# Ethernet.net
KiCad netlist of a schematic drawn in Altium Designer
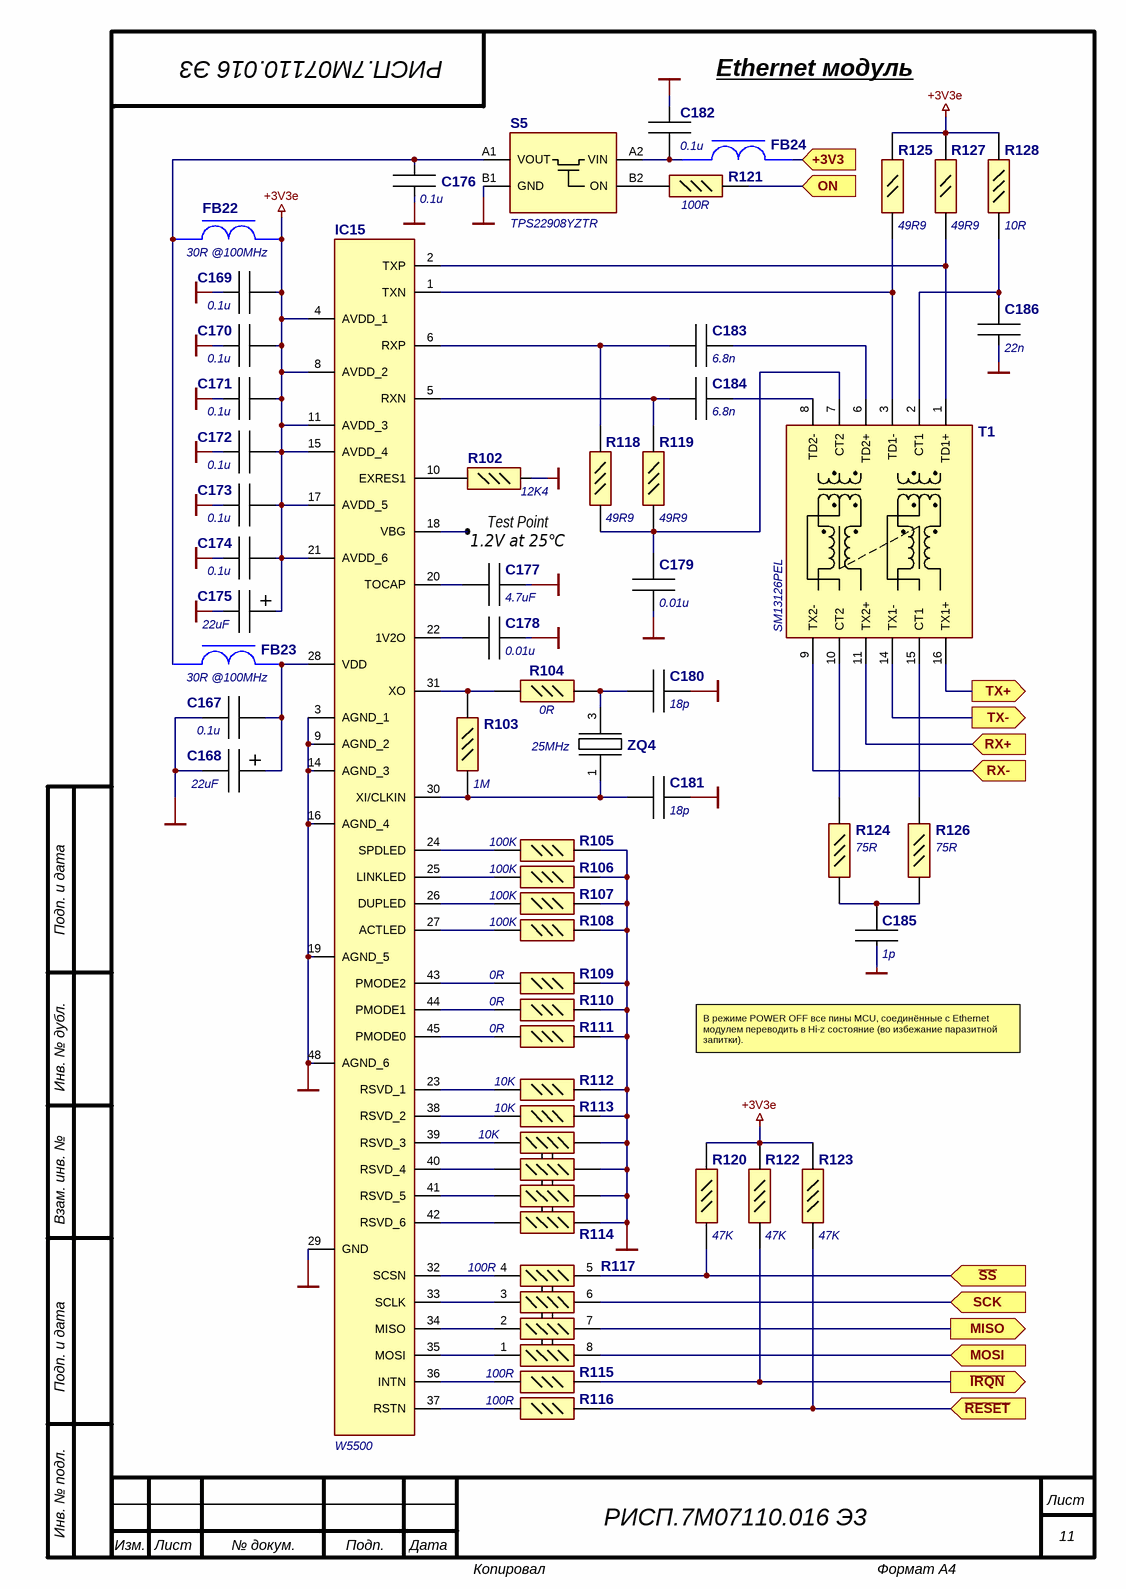
[diagram p0: Ethernet модуль.SchDoc]

(export (version "E")
  (design (tool "Eeschema 10.0.6"))
  (components
    (comp (ref "C167")
      (value "0.1u")
      (footprint ":CAP0402 100x50x50")
      (description "±10% 25V Ceramic Capacitor X7R 0402 (1005 Metric)")
      (fields
        (field (name "MANUFACTURER_PART_NUMBER") "GRM155R71E104KE14J")
        (field (name "MOUSER PART NUMBER") "81-GRM155R71E104KE4J")
      )
      (libsource (lib "Capacitors 0402") (part "GRM155R71E104KE14J"))
    )
    (comp (ref "C168")
      (value "22uF")
      (footprint ":CAP1206 C3216-18")
      (description "22µF Molded Tantalum Capacitors 6.3V 1206 (3216 Metric) 300mOhm @ 100kHz")
      (fields (field (name "MANUFACTURER_PART_NUMBER") "TPSA226K006R0300"))
      (libsource (lib "Capacitors 1206") (part "TPSA226K006R0300"))
    )
    (comp (ref "C169")
      (value "0.1u")
      (footprint ":CAP0402 100x50x50")
      (description "±10% 25V Ceramic Capacitor X7R 0402 (1005 Metric)")
      (fields
        (field (name "MANUFACTURER_PART_NUMBER") "GRM155R71E104KE14J")
        (field (name "MOUSER PART NUMBER") "81-GRM155R71E104KE4J")
      )
      (libsource (lib "Capacitors 0402") (part "GRM155R71E104KE14J"))
    )
    (comp (ref "C170")
      (value "0.1u")
      (footprint ":CAP0402 100x50x50")
      (description "±10% 25V Ceramic Capacitor X7R 0402 (1005 Metric)")
      (fields
        (field (name "MANUFACTURER_PART_NUMBER") "GRM155R71E104KE14J")
        (field (name "MOUSER PART NUMBER") "81-GRM155R71E104KE4J")
      )
      (libsource (lib "Capacitors 0402") (part "GRM155R71E104KE14J"))
    )
    (comp (ref "C171")
      (value "0.1u")
      (footprint ":CAP0402 100x50x50")
      (description "±10% 25V Ceramic Capacitor X7R 0402 (1005 Metric)")
      (fields
        (field (name "MANUFACTURER_PART_NUMBER") "GRM155R71E104KE14J")
        (field (name "MOUSER PART NUMBER") "81-GRM155R71E104KE4J")
      )
      (libsource (lib "Capacitors 0402") (part "GRM155R71E104KE14J"))
    )
    (comp (ref "C172")
      (value "0.1u")
      (footprint ":CAP0402 100x50x50")
      (description "±10% 25V Ceramic Capacitor X7R 0402 (1005 Metric)")
      (fields
        (field (name "MANUFACTURER_PART_NUMBER") "GRM155R71E104KE14J")
        (field (name "MOUSER PART NUMBER") "81-GRM155R71E104KE4J")
      )
      (libsource (lib "Capacitors 0402") (part "GRM155R71E104KE14J"))
    )
    (comp (ref "C173")
      (value "0.1u")
      (footprint ":CAP0402 100x50x50")
      (description "±10% 25V Ceramic Capacitor X7R 0402 (1005 Metric)")
      (fields
        (field (name "MANUFACTURER_PART_NUMBER") "GRM155R71E104KE14J")
        (field (name "MOUSER PART NUMBER") "81-GRM155R71E104KE4J")
      )
      (libsource (lib "Capacitors 0402") (part "GRM155R71E104KE14J"))
    )
    (comp (ref "C174")
      (value "0.1u")
      (footprint ":CAP0402 100x50x50")
      (description "±10% 25V Ceramic Capacitor X7R 0402 (1005 Metric)")
      (fields
        (field (name "MANUFACTURER_PART_NUMBER") "GRM155R71E104KE14J")
        (field (name "MOUSER PART NUMBER") "81-GRM155R71E104KE4J")
      )
      (libsource (lib "Capacitors 0402") (part "GRM155R71E104KE14J"))
    )
    (comp (ref "C175")
      (value "22uF")
      (footprint ":CAP1206 C3216-18")
      (description "22µF Molded Tantalum Capacitors 6.3V 1206 (3216 Metric) 300mOhm @ 100kHz")
      (fields (field (name "MANUFACTURER_PART_NUMBER") "TPSA226K006R0300"))
      (libsource (lib "Capacitors 1206") (part "TPSA226K006R0300"))
    )
    (comp (ref "C176")
      (value "0.1u")
      (footprint ":CAP0402 100x50x50")
      (description "±10% 25V Ceramic Capacitor X7R 0402 (1005 Metric)")
      (fields
        (field (name "MANUFACTURER_PART_NUMBER") "GRM155R71E104KE14J")
        (field (name "MOUSER PART NUMBER") "81-GRM155R71E104KE4J")
      )
      (libsource (lib "") (part "GRM155R71E104KE14J_1"))
    )
    (comp (ref "C177")
      (value "4.7uF")
      (footprint ":CAP0805 C2012X125")
      (description "CAP CER 4.7uF 25V X7R 0805")
      (fields (field (name "MANUFACTURER_PART_NUMBER") "GRM21BZ71E475KE15L"))
      (libsource (lib "Capacitors 0805") (part "GRM21BZ71E475KE15L"))
    )
    (comp (ref "C178")
      (value "0.01u")
      (footprint ":CAP0402 100x50x50")
      (description "±5% 35V Ceramic Capacitor C0G, NP0 0402 (1005 Metric)")
      (fields (field (name "MANUFACTURER_PART_NUMBER") "GRM1555CYA103JE01D"))
      (libsource (lib "Capacitors 0402") (part "GRM1555CYA103JE01D"))
    )
    (comp (ref "C179")
      (value "0.01u")
      (footprint ":CAP0402 100x50x50")
      (description "±5% 35V Ceramic Capacitor C0G, NP0 0402 (1005 Metric)")
      (fields (field (name "MANUFACTURER_PART_NUMBER") "GRM1555CYA103JE01D"))
      (libsource (lib "Capacitors 0402") (part "GRM1555CYA103JE01D"))
    )
    (comp (ref "C180")
      (value "18p")
      (footprint ":CAP0402 100x50x50")
      (description "CAP CER  50V C0G/NP0 0402")
      (fields (field (name "MANUFACTURER_PART_NUMBER") "GJM1555C1H180JB01D"))
      (libsource (lib "Capacitors 0402") (part "GJM1555C1H180JB01D"))
    )
    (comp (ref "C181")
      (value "18p")
      (footprint ":CAP0402 100x50x50")
      (description "CAP CER  50V C0G/NP0 0402")
      (fields (field (name "MANUFACTURER_PART_NUMBER") "GJM1555C1H180JB01D"))
      (libsource (lib "Capacitors 0402") (part "GJM1555C1H180JB01D"))
    )
    (comp (ref "C182")
      (value "0.1u")
      (footprint ":CAP0402 100x50x50")
      (description "±10% 25V Ceramic Capacitor X7R 0402 (1005 Metric)")
      (fields
        (field (name "MANUFACTURER_PART_NUMBER") "GRM155R71E104KE14J")
        (field (name "MOUSER PART NUMBER") "81-GRM155R71E104KE4J")
      )
      (libsource (lib "Capacitors 0402") (part "GRM155R71E104KE14J"))
    )
    (comp (ref "C183")
      (value "6.8n")
      (footprint ":CAP0402 100x50x50")
      (description "CAP CER  25V X7R 0402")
      (fields (field (name "MANUFACTURER_PART_NUMBER") "GCM155R71E682KA37D"))
      (libsource (lib "Capacitors 0402") (part "GCM155R71E682KA37D"))
    )
    (comp (ref "C184")
      (value "6.8n")
      (footprint ":CAP0402 100x50x50")
      (description "CAP CER  25V X7R 0402")
      (fields (field (name "MANUFACTURER_PART_NUMBER") "GCM155R71E682KA37D"))
      (libsource (lib "Capacitors 0402") (part "GCM155R71E682KA37D"))
    )
    (comp (ref "C185")
      (value "1p")
      (footprint ":CAP0402 100x50x50")
      (description "CAP CER  50V C0G/NP0 0402")
      (fields (field (name "MANUFACTURER_PART_NUMBER") "GJM1555C1H1R0BB01D"))
      (libsource (lib "Capacitors 0402") (part "GJM1555C1H1R0BB01D"))
    )
    (comp (ref "C186")
      (value "22n")
      (footprint ":CAP0402 100x50x50")
      (description "CAP CER  25V X7R 0402")
      (fields (field (name "MANUFACTURER_PART_NUMBER") "GCM155R71E223KA55D"))
      (libsource (lib "Capacitors 0402") (part "GCM155R71E223KA55D"))
    )
    (comp (ref "FB22")
      (value "30R @100MHz")
      (footprint ":FER BLM18SP300SN1D")
      (description "30 Ohms @ 100MHz 1 Power Line Ferrite Bead 0603 (1608 Metric) 6A 8mOhm")
      (fields
        (field (name "MANUFACTURER_PART_NUMBER") "BLM18SP300SN1D")
        (field (name "MOUSER PART NUMBER") "81-BLM18SP300SN1D")
      )
      (libsource (lib "Ferrite Bead") (part "BLM18SP300SN1D"))
    )
    (comp (ref "FB23")
      (value "30R @100MHz")
      (footprint ":FER BLM18SP300SN1D")
      (description "30 Ohms @ 100MHz 1 Power Line Ferrite Bead 0603 (1608 Metric) 6A 8mOhm")
      (fields
        (field (name "MANUFACTURER_PART_NUMBER") "BLM18SP300SN1D")
        (field (name "MOUSER PART NUMBER") "81-BLM18SP300SN1D")
      )
      (libsource (lib "Ferrite Bead") (part "BLM18SP300SN1D"))
    )
    (comp (ref "FB24")
      (value "30R @100MHz")
      (footprint ":FER BLM18SP300SN1D")
      (description "30 Ohms @ 100MHz 1 Power Line Ferrite Bead 0603 (1608 Metric) 6A 8mOhm")
      (fields
        (field (name "MANUFACTURER_PART_NUMBER") "BLM18SP300SN1D")
        (field (name "MOUSER PART NUMBER") "81-BLM18SP300SN1D")
      )
      (libsource (lib "Ferrite Bead") (part "BLM18SP300SN1D"))
    )
    (comp (ref "IC15")
      (value "W5500")
      (footprint ":QFP48 P900X900X160-48N")
      (description "Ethernet ICs 3in1 Enet Controller TCP/IP +MAC+PHY")
      (libsource (lib "Digital ICs") (part "W5500"))
    )
    (comp (ref "R102")
      (value "RC0402FR-07")
      (footprint ":RES0402")
      (fields (field (name "MANUFACTURER_PART_NUMBER (PART 2: VALUE)") "12K4"))
      (libsource (lib "Resistors 0402") (part "RC0402FR-07"))
    )
    (comp (ref "R103")
      (value "RC0402FR-07")
      (footprint ":RES0402")
      (fields (field (name "MANUFACTURER_PART_NUMBER (PART 2: VALUE)") "1M"))
      (libsource (lib "") (part "RC0402FR-07_3"))
    )
    (comp (ref "R104")
      (value "RC0402FR-07")
      (footprint ":RES0402")
      (fields (field (name "MANUFACTURER_PART_NUMBER (PART 2: VALUE)") "0R"))
      (libsource (lib "Resistors 0402") (part "RC0402FR-07"))
    )
    (comp (ref "R105")
      (value "RC0402FR-07")
      (footprint ":RES0402")
      (fields (field (name "MANUFACTURER_PART_NUMBER (PART 2: VALUE)") "100K"))
      (libsource (lib "Resistors 0402") (part "RC0402FR-07"))
    )
    (comp (ref "R106")
      (value "RC0402FR-07")
      (footprint ":RES0402")
      (fields (field (name "MANUFACTURER_PART_NUMBER (PART 2: VALUE)") "100K"))
      (libsource (lib "Resistors 0402") (part "RC0402FR-07"))
    )
    (comp (ref "R107")
      (value "RC0402FR-07")
      (footprint ":RES0402")
      (fields (field (name "MANUFACTURER_PART_NUMBER (PART 2: VALUE)") "100K"))
      (libsource (lib "Resistors 0402") (part "RC0402FR-07"))
    )
    (comp (ref "R108")
      (value "RC0402FR-07")
      (footprint ":RES0402")
      (fields (field (name "MANUFACTURER_PART_NUMBER (PART 2: VALUE)") "100K"))
      (libsource (lib "Resistors 0402") (part "RC0402FR-07"))
    )
    (comp (ref "R109")
      (value "RC0402FR-07")
      (footprint ":RES0402")
      (fields (field (name "MANUFACTURER_PART_NUMBER (PART 2: VALUE)") "0R"))
      (libsource (lib "Resistors 0402") (part "RC0402FR-07"))
    )
    (comp (ref "R110")
      (value "RC0402FR-07")
      (footprint ":RES0402")
      (fields (field (name "MANUFACTURER_PART_NUMBER (PART 2: VALUE)") "0R"))
      (libsource (lib "Resistors 0402") (part "RC0402FR-07"))
    )
    (comp (ref "R111")
      (value "RC0402FR-07")
      (footprint ":RES0402")
      (fields (field (name "MANUFACTURER_PART_NUMBER (PART 2: VALUE)") "0R"))
      (libsource (lib "Resistors 0402") (part "RC0402FR-07"))
    )
    (comp (ref "R112")
      (value "RC0402FR-07")
      (footprint ":RES0402")
      (fields (field (name "MANUFACTURER_PART_NUMBER (PART 2: VALUE)") "10K"))
      (libsource (lib "") (part "RC0402FR-07_1"))
    )
    (comp (ref "R113")
      (value "RC0402FR-07")
      (footprint ":RES0402")
      (fields (field (name "MANUFACTURER_PART_NUMBER (PART 2: VALUE)") "10K"))
      (libsource (lib "") (part "RC0402FR-07_1"))
    )
    (comp (ref "R114")
      (value "10K")
      (footprint ":RES0402x4")
      (fields (field (name "MANUFACTURER_PART_NUMBER") "EXB-N8V103JX"))
      (libsource (lib "Resistors Arrays") (part "EXB-N8V103JX"))
    )
    (comp (ref "R115")
      (value "RC0402FR-07")
      (footprint ":RES0402")
      (fields (field (name "MANUFACTURER_PART_NUMBER (PART 2: VALUE)") "100R"))
      (libsource (lib "Resistors 0402") (part "RC0402FR-07"))
    )
    (comp (ref "R116")
      (value "RC0402FR-07")
      (footprint ":RES0402")
      (fields (field (name "MANUFACTURER_PART_NUMBER (PART 2: VALUE)") "100R"))
      (libsource (lib "Resistors 0402") (part "RC0402FR-07"))
    )
    (comp (ref "R117")
      (value "100R")
      (footprint ":RES0402x4")
      (fields
        (field (name "MANUFACTURER_PART_NUMBER") "EXB-N8V101JX")
        (field (name "MOUSER PART NUMBER") "667-EXB-N8V101JX")
      )
      (libsource (lib "Resistors Arrays") (part "EXB-N8V101JX"))
    )
    (comp (ref "R118")
      (value "RC0402FR-07")
      (footprint ":RES0402")
      (fields (field (name "MANUFACTURER_PART_NUMBER (PART 2: VALUE)") "49R9"))
      (libsource (lib "") (part "RC0402FR-07_3"))
    )
    (comp (ref "R119")
      (value "RC0402FR-07")
      (footprint ":RES0402")
      (fields (field (name "MANUFACTURER_PART_NUMBER (PART 2: VALUE)") "49R9"))
      (libsource (lib "") (part "RC0402FR-07_3"))
    )
    (comp (ref "R120")
      (value "RC0402FR-07")
      (footprint ":RES0402")
      (fields (field (name "MANUFACTURER_PART_NUMBER (PART 2: VALUE)") "47K"))
      (libsource (lib "") (part "RC0402FR-07_3"))
    )
    (comp (ref "R121")
      (value "RC0402FR-07")
      (footprint ":RES0402")
      (fields (field (name "MANUFACTURER_PART_NUMBER (PART 2: VALUE)") "100R"))
      (libsource (lib "Resistors 0402") (part "RC0402FR-07"))
    )
    (comp (ref "R122")
      (value "RC0402FR-07")
      (footprint ":RES0402")
      (fields (field (name "MANUFACTURER_PART_NUMBER (PART 2: VALUE)") "47K"))
      (libsource (lib "") (part "RC0402FR-07_3"))
    )
    (comp (ref "R123")
      (value "RC0402FR-07")
      (footprint ":RES0402")
      (fields (field (name "MANUFACTURER_PART_NUMBER (PART 2: VALUE)") "47K"))
      (libsource (lib "") (part "RC0402FR-07_3"))
    )
    (comp (ref "R124")
      (value "RC0402FR-07")
      (footprint ":RES0402")
      (fields (field (name "MANUFACTURER_PART_NUMBER (PART 2: VALUE)") "75R"))
      (libsource (lib "") (part "RC0402FR-07_2"))
    )
    (comp (ref "R125")
      (value "49R9")
      (footprint ":RES0805")
      (description "49.9 Ohms ±1% 0.125W, 1/8W Chip Resistor 0805 (2012 Metric) Automotive AEC-Q200 Thick Film")
      (fields
        (field (name "MANUFACTURER_PART_NUMBER") "ERJ-6ENF49R9V")
        (field (name "MOUSER PART NUMBER") "667-ERJ-6ENF49R9V")
      )
      (libsource (lib "Resistors 0805") (part "ERJ-6ENF49R9V"))
    )
    (comp (ref "R126")
      (value "RC0402FR-07")
      (footprint ":RES0402")
      (fields (field (name "MANUFACTURER_PART_NUMBER (PART 2: VALUE)") "75R"))
      (libsource (lib "") (part "RC0402FR-07_2"))
    )
    (comp (ref "R127")
      (value "49R9")
      (footprint ":RES0805")
      (description "49.9 Ohms ±1% 0.125W, 1/8W Chip Resistor 0805 (2012 Metric) Automotive AEC-Q200 Thick Film")
      (fields
        (field (name "MANUFACTURER_PART_NUMBER") "ERJ-6ENF49R9V")
        (field (name "MOUSER PART NUMBER") "667-ERJ-6ENF49R9V")
      )
      (libsource (lib "Resistors 0805") (part "ERJ-6ENF49R9V"))
    )
    (comp (ref "R128")
      (value "RC0402FR-07")
      (footprint ":RES0402")
      (fields (field (name "MANUFACTURER_PART_NUMBER (PART 2: VALUE)") "10R"))
      (libsource (lib "") (part "RC0402FR-07_3"))
    )
    (comp (ref "S5")
      (value "TPS22908YZTR")
      (footprint ":BGA4 P90X90X50")
      (description "SPST Switch 3.6-V, 1-A, 28-mΩ")
      (fields (field (name "MOUSER PART NUMBER") "595-TPS22908YZTR"))
      (libsource (lib "Switching and Relays") (part "TPS22908YZTR"))
    )
    (comp (ref "T1")
      (value "SM13126PEL")
      (footprint ":TRAN SM13126PEL")
      (description "Transformers LAN 10/100 BASE-T")
      (fields (field (name "MOUSER PART NUMBER") "652-SM13126PEL"))
      (libsource (lib "Transformers") (part "SM13126PEL"))
    )
    (comp (ref "X3")
      (value "Big Circle Pad")
      (description "Большая круглая контактная площадка")
      (libsource (lib "Connectors") (part "Big Circle Pad"))
    )
    (comp (ref "ZQ4")
      (value "25MHz")
      (footprint ":RESO SXT22418FB48-25.000MT")
      (description "CRYSTAL 25MHz\r\n±10ppm Crystal 18pF 4-SMD\r\nESR: 80 Ohms")
      (fields (field (name "MANUFACTURER_PART_NUMBER") "SXT22418FB48-25.000MT"))
      (libsource (lib "Crystal and TXCO") (part "SXT22418FB48-25.000MT"))
    )
  )
  (nets
    (net (code "1") (name "+3V3e") (class "Default")
      (node (ref "C169") (pin "2") (pinfunction "2_2") (pintype "passive"))
      (node (ref "C170") (pin "2") (pinfunction "2_2") (pintype "passive"))
      (node (ref "C171") (pin "2") (pinfunction "2_2") (pintype "passive"))
      (node (ref "C172") (pin "2") (pinfunction "2_2") (pintype "passive"))
      (node (ref "C173") (pin "2") (pinfunction "2_2") (pintype "passive"))
      (node (ref "C174") (pin "2") (pinfunction "2_2") (pintype "passive"))
      (node (ref "C175") (pin "1") (pinfunction "+_1") (pintype "passive"))
      (node (ref "FB22") (pin "2") (pinfunction "2_2") (pintype "passive"))
      (node (ref "IC15") (pin "11") (pinfunction "AVDD_3_11") (pintype "passive"))
      (node (ref "IC15") (pin "15") (pinfunction "AVDD_4_15") (pintype "passive"))
      (node (ref "IC15") (pin "17") (pinfunction "AVDD_5_17") (pintype "passive"))
      (node (ref "IC15") (pin "21") (pinfunction "AVDD_6_21") (pintype "passive"))
      (node (ref "IC15") (pin "4") (pinfunction "AVDD_1_4") (pintype "passive"))
      (node (ref "IC15") (pin "8") (pinfunction "AVDD_2_8") (pintype "passive"))
      (node (ref "R120") (pin "2") (pinfunction "2_2") (pintype "passive"))
      (node (ref "R122") (pin "2") (pinfunction "2_2") (pintype "passive"))
      (node (ref "R123") (pin "2") (pinfunction "2_2") (pintype "passive"))
      (node (ref "R125") (pin "2") (pinfunction "2_2") (pintype "passive"))
      (node (ref "R127") (pin "2") (pinfunction "2_2") (pintype "passive"))
      (node (ref "R128") (pin "2") (pinfunction "2_2") (pintype "passive"))
    )
    (net (code "2") (name "/+3V3") (class "Default")
      (node (ref "FB24") (pin "2") (pinfunction "2_2") (pintype "passive"))
    )
    (net (code "3") (name "/MISO") (class "Default")
      (node (ref "R117") (pin "7") (pinfunction "7_7") (pintype "passive"))
    )
    (net (code "4") (name "/MOSI") (class "Default")
      (node (ref "R117") (pin "8") (pinfunction "8_8") (pintype "passive"))
    )
    (net (code "5") (name "/ON") (class "Default")
      (node (ref "R121") (pin "2") (pinfunction "2_2") (pintype "passive"))
    )
    (net (code "6") (name "/RX+") (class "Default")
      (node (ref "T1") (pin "11") (pinfunction "TX2+_11") (pintype "passive"))
    )
    (net (code "7") (name "/RX-") (class "Default")
      (node (ref "T1") (pin "9") (pinfunction "TX2-_9") (pintype "passive"))
    )
    (net (code "8") (name "/SCK") (class "Default")
      (node (ref "R117") (pin "6") (pinfunction "6_6") (pintype "passive"))
    )
    (net (code "9") (name "/TX+") (class "Default")
      (node (ref "T1") (pin "16") (pinfunction "TX1+_16") (pintype "passive"))
    )
    (net (code "10") (name "/TX-") (class "Default")
      (node (ref "T1") (pin "14") (pinfunction "TX1-_14") (pintype "passive"))
    )
    (net (code "11") (name "/~{IRQN}") (class "Default")
      (node (ref "R115") (pin "2") (pinfunction "2_2") (pintype "passive"))
      (node (ref "R122") (pin "1") (pinfunction "1_1") (pintype "passive"))
    )
    (net (code "12") (name "/~{RESET}") (class "Default")
      (node (ref "R116") (pin "2") (pinfunction "2_2") (pintype "passive"))
      (node (ref "R123") (pin "1") (pinfunction "1_1") (pintype "passive"))
    )
    (net (code "13") (name "/~{SS}") (class "Default")
      (node (ref "R117") (pin "5") (pinfunction "5_5") (pintype "passive"))
      (node (ref "R120") (pin "1") (pinfunction "1_1") (pintype "passive"))
    )
    (net (code "14") (name "GND") (class "Default")
      (node (ref "C167") (pin "1") (pinfunction "1_1") (pintype "passive"))
      (node (ref "C168") (pin "2") (pinfunction "2_2") (pintype "passive"))
      (node (ref "C169") (pin "1") (pinfunction "1_1") (pintype "passive"))
      (node (ref "C170") (pin "1") (pinfunction "1_1") (pintype "passive"))
      (node (ref "C171") (pin "1") (pinfunction "1_1") (pintype "passive"))
      (node (ref "C172") (pin "1") (pinfunction "1_1") (pintype "passive"))
      (node (ref "C173") (pin "1") (pinfunction "1_1") (pintype "passive"))
      (node (ref "C174") (pin "1") (pinfunction "1_1") (pintype "passive"))
      (node (ref "C175") (pin "2") (pinfunction "2_2") (pintype "passive"))
      (node (ref "C176") (pin "2") (pinfunction "2_2") (pintype "passive"))
      (node (ref "C177") (pin "2") (pinfunction "2_2") (pintype "passive"))
      (node (ref "C178") (pin "2") (pinfunction "2_2") (pintype "passive"))
      (node (ref "C179") (pin "1") (pinfunction "1_1") (pintype "passive"))
      (node (ref "C180") (pin "2") (pinfunction "2_2") (pintype "passive"))
      (node (ref "C181") (pin "2") (pinfunction "2_2") (pintype "passive"))
      (node (ref "C182") (pin "2") (pinfunction "2_2") (pintype "passive"))
      (node (ref "C185") (pin "2") (pinfunction "2_2") (pintype "passive"))
      (node (ref "C186") (pin "1") (pinfunction "1_1") (pintype "passive"))
      (node (ref "IC15") (pin "14") (pinfunction "AGND_3_14") (pintype "passive"))
      (node (ref "IC15") (pin "16") (pinfunction "AGND_4_16") (pintype "passive"))
      (node (ref "IC15") (pin "19") (pinfunction "AGND_5_19") (pintype "passive"))
      (node (ref "IC15") (pin "29") (pinfunction "GND_29") (pintype "passive"))
      (node (ref "IC15") (pin "3") (pinfunction "AGND_1_3") (pintype "passive"))
      (node (ref "IC15") (pin "48") (pinfunction "AGND_6_48") (pintype "passive"))
      (node (ref "IC15") (pin "9") (pinfunction "AGND_2_9") (pintype "passive"))
      (node (ref "R102") (pin "2") (pinfunction "2_2") (pintype "passive"))
      (node (ref "R105") (pin "2") (pinfunction "2_2") (pintype "passive"))
      (node (ref "R106") (pin "2") (pinfunction "2_2") (pintype "passive"))
      (node (ref "R107") (pin "2") (pinfunction "2_2") (pintype "passive"))
      (node (ref "R108") (pin "2") (pinfunction "2_2") (pintype "passive"))
      (node (ref "R109") (pin "2") (pinfunction "2_2") (pintype "passive"))
      (node (ref "R110") (pin "2") (pinfunction "2_2") (pintype "passive"))
      (node (ref "R111") (pin "2") (pinfunction "2_2") (pintype "passive"))
      (node (ref "R112") (pin "1") (pinfunction "1_1") (pintype "passive"))
      (node (ref "R113") (pin "1") (pinfunction "1_1") (pintype "passive"))
      (node (ref "R114") (pin "5") (pinfunction "5_5") (pintype "passive"))
      (node (ref "R114") (pin "6") (pinfunction "6_6") (pintype "passive"))
      (node (ref "R114") (pin "7") (pinfunction "7_7") (pintype "passive"))
      (node (ref "R114") (pin "8") (pinfunction "8_8") (pintype "passive"))
      (node (ref "S5") (pin "B1") (pinfunction "GND_B1") (pintype "passive"))
    )
    (net (code "15") (name "Net-(C168-+)") (class "Default")
      (node (ref "C167") (pin "2") (pinfunction "2_2") (pintype "passive"))
      (node (ref "C168") (pin "1") (pinfunction "+_1") (pintype "passive"))
      (node (ref "FB23") (pin "2") (pinfunction "2_2") (pintype "passive"))
      (node (ref "IC15") (pin "28") (pinfunction "VDD_28") (pintype "passive"))
    )
    (net (code "16") (name "Net-(C179-Pad2)") (class "Default")
      (node (ref "C179") (pin "2") (pinfunction "2_2") (pintype "passive"))
      (node (ref "R118") (pin "1") (pinfunction "1_1") (pintype "passive"))
      (node (ref "R119") (pin "1") (pinfunction "1_1") (pintype "passive"))
      (node (ref "T1") (pin "7") (pinfunction "CT2_7") (pintype "passive"))
    )
    (net (code "17") (name "Net-(C180-Pad1)") (class "Default")
      (node (ref "C180") (pin "1") (pinfunction "1_1") (pintype "passive"))
      (node (ref "R104") (pin "2") (pinfunction "2_2") (pintype "passive"))
      (node (ref "ZQ4") (pin "3") (pinfunction "3_3") (pintype "passive"))
    )
    (net (code "18") (name "Net-(C185-Pad1)") (class "Default")
      (node (ref "C185") (pin "1") (pinfunction "1_1") (pintype "passive"))
      (node (ref "R124") (pin "2") (pinfunction "2_2") (pintype "passive"))
      (node (ref "R126") (pin "2") (pinfunction "2_2") (pintype "passive"))
    )
    (net (code "19") (name "Net-(C186-Pad2)") (class "Default")
      (node (ref "C186") (pin "2") (pinfunction "2_2") (pintype "passive"))
      (node (ref "R128") (pin "1") (pinfunction "1_1") (pintype "passive"))
      (node (ref "T1") (pin "2") (pinfunction "CT1_2") (pintype "passive"))
    )
    (net (code "20") (name "Net-(IC15-1V2O)") (class "Default")
      (node (ref "C178") (pin "1") (pinfunction "1_1") (pintype "passive"))
      (node (ref "IC15") (pin "22") (pinfunction "1V2O_22") (pintype "passive"))
    )
    (net (code "21") (name "Net-(IC15-ACTLED)") (class "Default")
      (node (ref "IC15") (pin "27") (pinfunction "ACTLED_27") (pintype "passive"))
      (node (ref "R108") (pin "1") (pinfunction "1_1") (pintype "passive"))
    )
    (net (code "22") (name "Net-(IC15-DUPLED)") (class "Default")
      (node (ref "IC15") (pin "26") (pinfunction "DUPLED_26") (pintype "passive"))
      (node (ref "R107") (pin "1") (pinfunction "1_1") (pintype "passive"))
    )
    (net (code "23") (name "Net-(IC15-EXRES1)") (class "Default")
      (node (ref "IC15") (pin "10") (pinfunction "EXRES1_10") (pintype "passive"))
      (node (ref "R102") (pin "1") (pinfunction "1_1") (pintype "passive"))
    )
    (net (code "24") (name "Net-(IC15-INTN)") (class "Default")
      (node (ref "IC15") (pin "36") (pinfunction "INTN_36") (pintype "passive"))
      (node (ref "R115") (pin "1") (pinfunction "1_1") (pintype "passive"))
    )
    (net (code "25") (name "Net-(IC15-LINKLED)") (class "Default")
      (node (ref "IC15") (pin "25") (pinfunction "LINKLED_25") (pintype "passive"))
      (node (ref "R106") (pin "1") (pinfunction "1_1") (pintype "passive"))
    )
    (net (code "26") (name "Net-(IC15-MISO)") (class "Default")
      (node (ref "IC15") (pin "34") (pinfunction "MISO_34") (pintype "passive"))
      (node (ref "R117") (pin "2") (pinfunction "2_2") (pintype "passive"))
    )
    (net (code "27") (name "Net-(IC15-MOSI)") (class "Default")
      (node (ref "IC15") (pin "35") (pinfunction "MOSI_35") (pintype "passive"))
      (node (ref "R117") (pin "1") (pinfunction "1_1") (pintype "passive"))
    )
    (net (code "28") (name "Net-(IC15-PMODE0)") (class "Default")
      (node (ref "IC15") (pin "45") (pinfunction "PMODE0_45") (pintype "passive"))
      (node (ref "R111") (pin "1") (pinfunction "1_1") (pintype "passive"))
    )
    (net (code "29") (name "Net-(IC15-PMODE1)") (class "Default")
      (node (ref "IC15") (pin "44") (pinfunction "PMODE1_44") (pintype "passive"))
      (node (ref "R110") (pin "1") (pinfunction "1_1") (pintype "passive"))
    )
    (net (code "30") (name "Net-(IC15-PMODE2)") (class "Default")
      (node (ref "IC15") (pin "43") (pinfunction "PMODE2_43") (pintype "passive"))
      (node (ref "R109") (pin "1") (pinfunction "1_1") (pintype "passive"))
    )
    (net (code "31") (name "Net-(IC15-RSTN)") (class "Default")
      (node (ref "IC15") (pin "37") (pinfunction "RSTN_37") (pintype "passive"))
      (node (ref "R116") (pin "1") (pinfunction "1_1") (pintype "passive"))
    )
    (net (code "32") (name "Net-(IC15-RSVD_1)") (class "Default")
      (node (ref "IC15") (pin "23") (pinfunction "RSVD_1_23") (pintype "passive"))
      (node (ref "R112") (pin "2") (pinfunction "2_2") (pintype "passive"))
    )
    (net (code "33") (name "Net-(IC15-RSVD_2)") (class "Default")
      (node (ref "IC15") (pin "38") (pinfunction "RSVD_2_38") (pintype "passive"))
      (node (ref "R113") (pin "2") (pinfunction "2_2") (pintype "passive"))
    )
    (net (code "34") (name "Net-(IC15-RSVD_3)") (class "Default")
      (node (ref "IC15") (pin "39") (pinfunction "RSVD_3_39") (pintype "passive"))
      (node (ref "R114") (pin "4") (pinfunction "4_4") (pintype "passive"))
    )
    (net (code "35") (name "Net-(IC15-RSVD_4)") (class "Default")
      (node (ref "IC15") (pin "40") (pinfunction "RSVD_4_40") (pintype "passive"))
      (node (ref "R114") (pin "3") (pinfunction "3_3") (pintype "passive"))
    )
    (net (code "36") (name "Net-(IC15-RSVD_5)") (class "Default")
      (node (ref "IC15") (pin "41") (pinfunction "RSVD_5_41") (pintype "passive"))
      (node (ref "R114") (pin "2") (pinfunction "2_2") (pintype "passive"))
    )
    (net (code "37") (name "Net-(IC15-RSVD_6)") (class "Default")
      (node (ref "IC15") (pin "42") (pinfunction "RSVD_6_42") (pintype "passive"))
      (node (ref "R114") (pin "1") (pinfunction "1_1") (pintype "passive"))
    )
    (net (code "38") (name "Net-(IC15-RXN)") (class "Default")
      (node (ref "C184") (pin "1") (pinfunction "1_1") (pintype "passive"))
      (node (ref "IC15") (pin "5") (pinfunction "RXN_5") (pintype "passive"))
      (node (ref "R119") (pin "2") (pinfunction "2_2") (pintype "passive"))
    )
    (net (code "39") (name "Net-(IC15-RXP)") (class "Default")
      (node (ref "C183") (pin "1") (pinfunction "1_1") (pintype "passive"))
      (node (ref "IC15") (pin "6") (pinfunction "RXP_6") (pintype "passive"))
      (node (ref "R118") (pin "2") (pinfunction "2_2") (pintype "passive"))
    )
    (net (code "40") (name "Net-(IC15-SCLK)") (class "Default")
      (node (ref "IC15") (pin "33") (pinfunction "SCLK_33") (pintype "passive"))
      (node (ref "R117") (pin "3") (pinfunction "3_3") (pintype "passive"))
    )
    (net (code "41") (name "Net-(IC15-SCSN)") (class "Default")
      (node (ref "IC15") (pin "32") (pinfunction "SCSN_32") (pintype "passive"))
      (node (ref "R117") (pin "4") (pinfunction "4_4") (pintype "passive"))
    )
    (net (code "42") (name "Net-(IC15-SPDLED)") (class "Default")
      (node (ref "IC15") (pin "24") (pinfunction "SPDLED_24") (pintype "passive"))
      (node (ref "R105") (pin "1") (pinfunction "1_1") (pintype "passive"))
    )
    (net (code "43") (name "Net-(IC15-TOCAP)") (class "Default")
      (node (ref "C177") (pin "1") (pinfunction "1_1") (pintype "passive"))
      (node (ref "IC15") (pin "20") (pinfunction "TOCAP_20") (pintype "passive"))
    )
    (net (code "44") (name "Net-(IC15-TXN)") (class "Default")
      (node (ref "IC15") (pin "1") (pinfunction "TXN_1") (pintype "passive"))
      (node (ref "R125") (pin "1") (pinfunction "1_1") (pintype "passive"))
      (node (ref "T1") (pin "3") (pinfunction "TD1-_3") (pintype "passive"))
    )
    (net (code "45") (name "Net-(IC15-TXP)") (class "Default")
      (node (ref "IC15") (pin "2") (pinfunction "TXP_2") (pintype "passive"))
      (node (ref "R127") (pin "1") (pinfunction "1_1") (pintype "passive"))
      (node (ref "T1") (pin "1") (pinfunction "TD1+_1") (pintype "passive"))
    )
    (net (code "46") (name "Net-(IC15-VBG)") (class "Default")
      (node (ref "IC15") (pin "18") (pinfunction "VBG_18") (pintype "passive"))
      (node (ref "X3") (pin "1") (pinfunction "1_1") (pintype "passive"))
    )
    (net (code "47") (name "Net-(IC15-XI{slash}CLKIN)") (class "Default")
      (node (ref "C181") (pin "1") (pinfunction "1_1") (pintype "passive"))
      (node (ref "IC15") (pin "30") (pinfunction "XI/CLKIN_30") (pintype "passive"))
      (node (ref "R103") (pin "1") (pinfunction "1_1") (pintype "passive"))
      (node (ref "ZQ4") (pin "1") (pinfunction "1_1") (pintype "passive"))
    )
    (net (code "48") (name "Net-(IC15-XO)") (class "Default")
      (node (ref "IC15") (pin "31") (pinfunction "XO_31") (pintype "passive"))
      (node (ref "R103") (pin "2") (pinfunction "2_2") (pintype "passive"))
      (node (ref "R104") (pin "1") (pinfunction "1_1") (pintype "passive"))
    )
    (net (code "49") (name "Net-(R124-Pad1)") (class "Default")
      (node (ref "R124") (pin "1") (pinfunction "1_1") (pintype "passive"))
      (node (ref "T1") (pin "10") (pinfunction "CT2_10") (pintype "passive"))
    )
    (net (code "50") (name "Net-(R126-Pad1)") (class "Default")
      (node (ref "R126") (pin "1") (pinfunction "1_1") (pintype "passive"))
      (node (ref "T1") (pin "15") (pinfunction "CT1_15") (pintype "passive"))
    )
    (net (code "51") (name "Net-(S5-ON)") (class "Default")
      (node (ref "R121") (pin "1") (pinfunction "1_1") (pintype "passive"))
      (node (ref "S5") (pin "B2") (pinfunction "ON_B2") (pintype "passive"))
    )
    (net (code "52") (name "Net-(S5-VIN)") (class "Default")
      (node (ref "C182") (pin "1") (pinfunction "1_1") (pintype "passive"))
      (node (ref "FB24") (pin "1") (pinfunction "1_1") (pintype "passive"))
      (node (ref "S5") (pin "A2") (pinfunction "VIN_A2") (pintype "passive"))
    )
    (net (code "53") (name "Net-(S5-VOUT)") (class "Default")
      (node (ref "C176") (pin "1") (pinfunction "1_1") (pintype "passive"))
      (node (ref "FB22") (pin "1") (pinfunction "1_1") (pintype "passive"))
      (node (ref "FB23") (pin "1") (pinfunction "1_1") (pintype "passive"))
      (node (ref "S5") (pin "A1") (pinfunction "VOUT_A1") (pintype "passive"))
    )
    (net (code "54") (name "Net-(T1-TD2+)") (class "Default")
      (node (ref "C183") (pin "2") (pinfunction "2_2") (pintype "passive"))
      (node (ref "T1") (pin "6") (pinfunction "TD2+_6") (pintype "passive"))
    )
    (net (code "55") (name "Net-(T1-TD2-)") (class "Default")
      (node (ref "C184") (pin "2") (pinfunction "2_2") (pintype "passive"))
      (node (ref "T1") (pin "8") (pinfunction "TD2-_8") (pintype "passive"))
    )
  )
)
